# XKT3619_wireless_charging_driver.net
KiCad netlist of a schematic drawn in Altium Designer
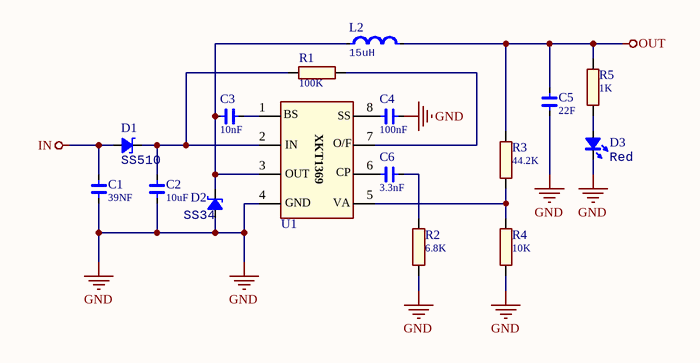
[diagram p0: XKT3619_wireless_charging_driver.SchDoc]

(export (version "E")
  (design (tool "Eeschema 10.0.6"))
  (components
    (comp (ref "C1")
      (value "39NF")
      (footprint "CAP_1206")
      (fields (field (name "Comment") "Cap"))
      (libsource (lib "Passive") (part "Cap"))
    )
    (comp (ref "C2")
      (value "10uF")
      (footprint "CAP_1206")
      (fields (field (name "Comment") "Cap"))
      (libsource (lib "Passive") (part "Cap"))
    )
    (comp (ref "C3")
      (value "10nF")
      (footprint "CAP_0603")
      (fields (field (name "Comment") "Cap"))
      (libsource (lib "") (part "Cap_1"))
    )
    (comp (ref "C4")
      (value "100nF")
      (footprint "CAP_0603")
      (fields (field (name "Comment") "Cap"))
      (libsource (lib "") (part "Cap_1"))
    )
    (comp (ref "C5")
      (value "22F")
      (footprint "CAP_1206")
      (fields (field (name "Comment") "Cap"))
      (libsource (lib "Passive") (part "Cap"))
    )
    (comp (ref "C6")
      (value "3.3nF")
      (footprint "CAP_0603")
      (fields (field (name "Comment") "Cap"))
      (libsource (lib "") (part "Cap_1"))
    )
    (comp (ref "D1")
      (value "SS510")
      (footprint "DO-214AB")
      (description "Schottky Diode")
      (libsource (lib "Active") (part "SchottkyDiode"))
    )
    (comp (ref "D2")
      (value "SS34")
      (footprint "DO-214AC")
      (description "Schottky Diode")
      (libsource (lib "Active") (part "SchottkyDiode"))
    )
    (comp (ref "D3")
      (value "Red")
      (footprint "LED_0805")
      (description "LED")
      (libsource (lib "Active") (part "LED"))
    )
    (comp (ref "L2")
      (value "15uH")
      (footprint "IND_CD75")
      (description "Inductor")
      (fields (field (name "Comment") "Ind"))
      (libsource (lib "Passive") (part "Ind"))
    )
    (comp (ref "R1")
      (value "100K")
      (footprint "RES_0603")
      (fields (field (name "Comment") "Res"))
      (libsource (lib "") (part "Res_1"))
    )
    (comp (ref "R2")
      (value "6.8K")
      (footprint "RES_0603")
      (fields (field (name "Comment") "Res"))
      (libsource (lib "Passive") (part "Res"))
    )
    (comp (ref "R3")
      (value "44.2K")
      (footprint "RES_0603")
      (fields (field (name "Comment") "Res"))
      (libsource (lib "Passive") (part "Res"))
    )
    (comp (ref "R4")
      (value "10K")
      (footprint "RES_0603")
      (fields (field (name "Comment") "Res"))
      (libsource (lib "Passive") (part "Res"))
    )
    (comp (ref "R5")
      (value "1K")
      (footprint "RES_0805")
      (fields (field (name "Comment") "Res"))
      (libsource (lib "Passive") (part "Res"))
    )
    (comp (ref "U1")
      (value "XLT-3169")
      (footprint "SOP8_M")
      (description "XKT-3169 是芯科泰无线充电系列通用接收集成电路，体积小输出功率大，可配合各种无线充电方案应用，电路简单使用方便")
      (libsource (lib "Misc") (part "XLT-3169"))
    )
  )
  (nets
    (net (code "1") (name "GND") (class "Default")
      (node (ref "C1") (pin "1") (pinfunction "1_1") (pintype "passive"))
      (node (ref "C2") (pin "1") (pinfunction "1_1") (pintype "passive"))
      (node (ref "C4") (pin "2") (pinfunction "2_2") (pintype "passive"))
      (node (ref "C5") (pin "1") (pinfunction "1_1") (pintype "passive"))
      (node (ref "D2") (pin "1") (pinfunction "A_1") (pintype "passive"))
      (node (ref "D3") (pin "2") (pinfunction "K_2") (pintype "passive"))
      (node (ref "R2") (pin "1") (pinfunction "1_1") (pintype "passive"))
      (node (ref "R4") (pin "1") (pinfunction "1_1") (pintype "passive"))
      (node (ref "U1") (pin "4") (pinfunction "GND_4") (pintype "passive"))
    )
    (net (code "2") (name "IN") (class "Default")
      (node (ref "C1") (pin "2") (pinfunction "2_2") (pintype "passive"))
      (node (ref "D1") (pin "1") (pinfunction "A_1") (pintype "passive"))
    )
    (net (code "3") (name "Net-(C6-Pad2)") (class "Default")
      (node (ref "C6") (pin "2") (pinfunction "2_2") (pintype "passive"))
      (node (ref "R2") (pin "2") (pinfunction "2_2") (pintype "passive"))
    )
    (net (code "4") (name "Net-(D1-K)") (class "Default")
      (node (ref "C2") (pin "2") (pinfunction "2_2") (pintype "passive"))
      (node (ref "D1") (pin "2") (pinfunction "K_2") (pintype "passive"))
      (node (ref "R1") (pin "1") (pinfunction "1_1") (pintype "passive"))
      (node (ref "U1") (pin "2") (pinfunction "IN_2") (pintype "passive"))
    )
    (net (code "5") (name "Net-(D2-K)") (class "Default")
      (node (ref "C3") (pin "1") (pinfunction "1_1") (pintype "passive"))
      (node (ref "D2") (pin "2") (pinfunction "K_2") (pintype "passive"))
      (node (ref "L2") (pin "1") (pinfunction "1_1") (pintype "passive"))
      (node (ref "U1") (pin "3") (pinfunction "OUT_3") (pintype "passive"))
    )
    (net (code "6") (name "Net-(D3-A)") (class "Default")
      (node (ref "D3") (pin "1") (pinfunction "A_1") (pintype "passive"))
      (node (ref "R5") (pin "1") (pinfunction "1_1") (pintype "passive"))
    )
    (net (code "7") (name "Net-(U1-BS)") (class "Default")
      (node (ref "C3") (pin "2") (pinfunction "2_2") (pintype "passive"))
      (node (ref "U1") (pin "1") (pinfunction "BS_1") (pintype "passive"))
    )
    (net (code "8") (name "Net-(U1-CP)") (class "Default")
      (node (ref "C6") (pin "1") (pinfunction "1_1") (pintype "passive"))
      (node (ref "U1") (pin "6") (pinfunction "CP_6") (pintype "passive"))
    )
    (net (code "9") (name "Net-(U1-O{slash}F)") (class "Default")
      (node (ref "R1") (pin "2") (pinfunction "2_2") (pintype "passive"))
      (node (ref "U1") (pin "7") (pinfunction "O/F_7") (pintype "passive"))
    )
    (net (code "10") (name "Net-(U1-SS)") (class "Default")
      (node (ref "C4") (pin "1") (pinfunction "1_1") (pintype "passive"))
      (node (ref "U1") (pin "8") (pinfunction "SS_8") (pintype "passive"))
    )
    (net (code "11") (name "Net-(U1-VA)") (class "Default")
      (node (ref "R3") (pin "1") (pinfunction "1_1") (pintype "passive"))
      (node (ref "R4") (pin "2") (pinfunction "2_2") (pintype "passive"))
      (node (ref "U1") (pin "5") (pinfunction "VA_5") (pintype "passive"))
    )
    (net (code "12") (name "OUT") (class "Default")
      (node (ref "C5") (pin "2") (pinfunction "2_2") (pintype "passive"))
      (node (ref "L2") (pin "2") (pinfunction "2_2") (pintype "passive"))
      (node (ref "R3") (pin "2") (pinfunction "2_2") (pintype "passive"))
      (node (ref "R5") (pin "2") (pinfunction "2_2") (pintype "passive"))
    )
  )
)
